# TwoArmedBandit_old.net
KiCad netlist of a schematic drawn in EAGLE
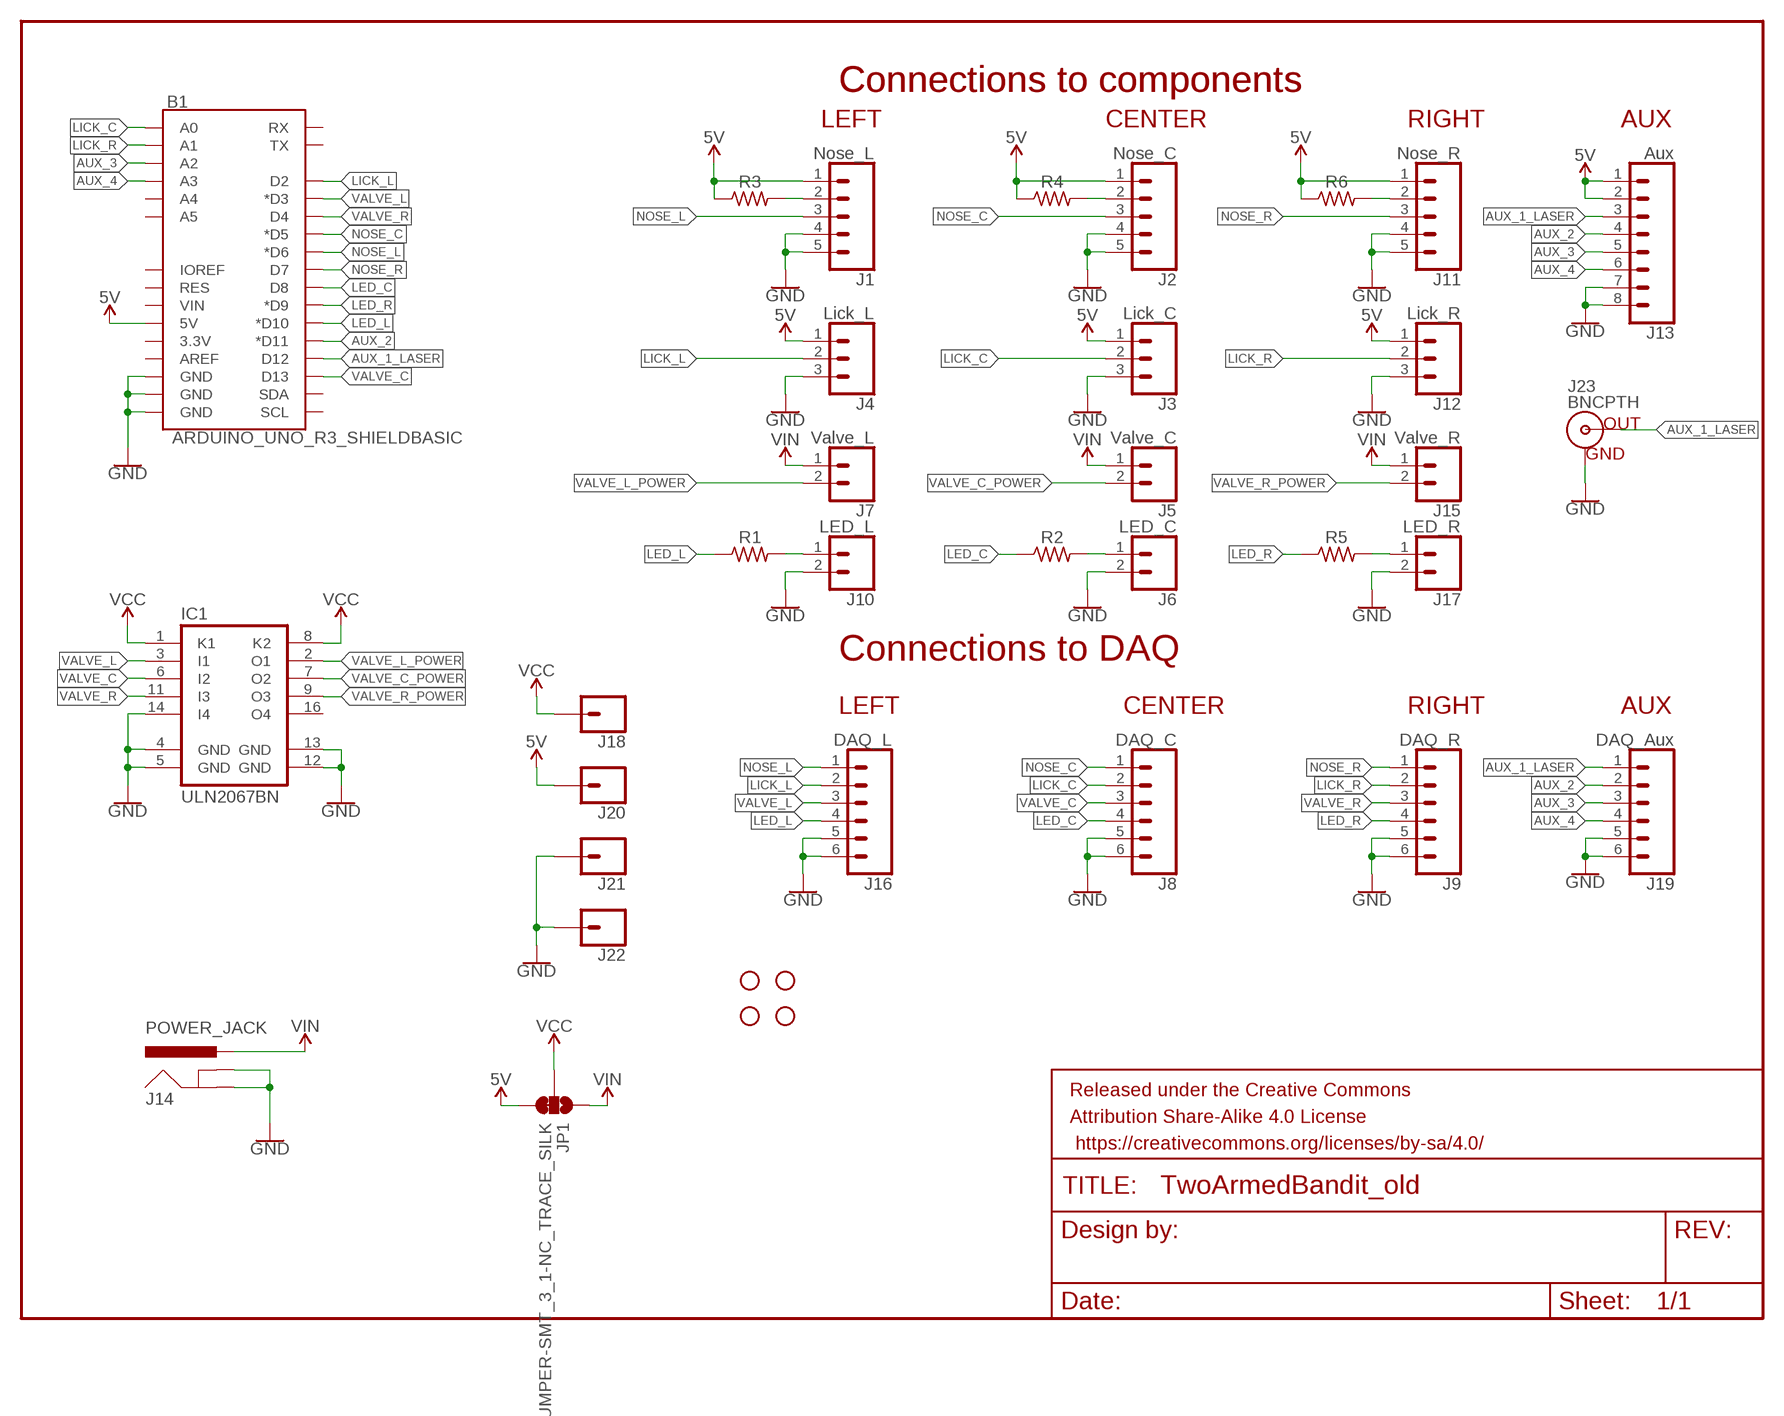
[diagram p0: schematic, sheet 1]

(export (version "E")
  (design (tool "Eeschema 10.0.6"))
  (components
    (comp (ref "B1")
      (value "ARDUINO_UNO_R3_SHIELDBASIC")
      (footprint "eagle-import:UNO_R3_SHIELD")
      (libsource (lib "eagle-import") (part "ARDUINO_UNO_R3_SHIELDBASIC"))
    )
    (comp (ref "FRAME1")
      (value "FRAME-LETTERNO_PACKAGE")
      (footprint "eagle-import:DUMMY")
      (fields (field (name "DESIGNER") "Nobody"))
      (libsource (lib "eagle-import") (part "FRAME-LETTERNO_PACKAGE"))
    )
    (comp (ref "H1")
      (value "STAND-OFF")
      (footprint "eagle-import:STAND-OFF")
      (libsource (lib "eagle-import") (part "STAND-OFF"))
    )
    (comp (ref "H2")
      (value "STAND-OFF")
      (footprint "eagle-import:STAND-OFF")
      (libsource (lib "eagle-import") (part "STAND-OFF"))
    )
    (comp (ref "H3")
      (value "STAND-OFF")
      (footprint "eagle-import:STAND-OFF")
      (libsource (lib "eagle-import") (part "STAND-OFF"))
    )
    (comp (ref "H4")
      (value "STAND-OFF")
      (footprint "eagle-import:STAND-OFF")
      (libsource (lib "eagle-import") (part "STAND-OFF"))
    )
    (comp (ref "IC1")
      (value "ULN2067BN")
      (footprint "eagle-import:DIL16")
      (libsource (lib "eagle-import") (part "ULN2067BN"))
    )
    (comp (ref "J1")
      (value "Nose_L")
      (footprint "eagle-import:SCREWTERMINAL-3.5MM-5")
      (libsource (lib "eagle-import") (part "CONN_05SCREW"))
    )
    (comp (ref "J2")
      (value "Nose_C")
      (footprint "eagle-import:SCREWTERMINAL-3.5MM-5")
      (libsource (lib "eagle-import") (part "CONN_05SCREW"))
    )
    (comp (ref "J3")
      (value "Lick_C")
      (footprint "eagle-import:1X03")
      (libsource (lib "eagle-import") (part "CONN_03"))
    )
    (comp (ref "J4")
      (value "Lick_L")
      (footprint "eagle-import:1X03")
      (libsource (lib "eagle-import") (part "CONN_03"))
    )
    (comp (ref "J5")
      (value "Valve_C")
      (footprint "eagle-import:1X02")
      (libsource (lib "eagle-import") (part "CONN_02"))
    )
    (comp (ref "J6")
      (value "LED_C")
      (footprint "eagle-import:1X02")
      (libsource (lib "eagle-import") (part "CONN_02"))
    )
    (comp (ref "J7")
      (value "Valve_L")
      (footprint "eagle-import:1X02")
      (libsource (lib "eagle-import") (part "CONN_02"))
    )
    (comp (ref "J8")
      (value "DAQ_C")
      (footprint "eagle-import:SCREWTERMINAL-3.5MM-6")
      (libsource (lib "eagle-import") (part "CONN_063.5MM-6"))
    )
    (comp (ref "J9")
      (value "DAQ_R")
      (footprint "eagle-import:SCREWTERMINAL-3.5MM-6")
      (libsource (lib "eagle-import") (part "CONN_063.5MM-6"))
    )
    (comp (ref "J10")
      (value "LED_L")
      (footprint "eagle-import:1X02")
      (libsource (lib "eagle-import") (part "CONN_02"))
    )
    (comp (ref "J11")
      (value "Nose_R")
      (footprint "eagle-import:SCREWTERMINAL-3.5MM-5")
      (libsource (lib "eagle-import") (part "CONN_05SCREW"))
    )
    (comp (ref "J12")
      (value "Lick_R")
      (footprint "eagle-import:1X03")
      (libsource (lib "eagle-import") (part "CONN_03"))
    )
    (comp (ref "J13")
      (value "Aux")
      (footprint "eagle-import:1X08")
      (libsource (lib "eagle-import") (part "CONN_08{dblquote}"))
    )
    (comp (ref "J14")
      (value "POWER_JACK")
      (footprint "eagle-import:POWER_JACK_PTH")
      (libsource (lib "eagle-import") (part "POWER_JACK"))
    )
    (comp (ref "J15")
      (value "Valve_R")
      (footprint "eagle-import:1X02")
      (libsource (lib "eagle-import") (part "CONN_02"))
    )
    (comp (ref "J16")
      (value "DAQ_L")
      (footprint "eagle-import:SCREWTERMINAL-3.5MM-6")
      (libsource (lib "eagle-import") (part "CONN_063.5MM-6"))
    )
    (comp (ref "J17")
      (value "LED_R")
      (footprint "eagle-import:1X02")
      (libsource (lib "eagle-import") (part "CONN_02"))
    )
    (comp (ref "J18")
      (value "CONN_01PTH_2MM")
      (footprint "eagle-import:1X01_2MM")
      (libsource (lib "eagle-import") (part "CONN_01PTH_2MM"))
    )
    (comp (ref "J19")
      (value "DAQ_Aux")
      (footprint "eagle-import:SCREWTERMINAL-3.5MM-6")
      (libsource (lib "eagle-import") (part "CONN_063.5MM-6"))
    )
    (comp (ref "J20")
      (value "CONN_01PTH_2MM")
      (footprint "eagle-import:1X01_2MM")
      (libsource (lib "eagle-import") (part "CONN_01PTH_2MM"))
    )
    (comp (ref "J21")
      (value "CONN_01PTH_2MM")
      (footprint "eagle-import:1X01_2MM")
      (libsource (lib "eagle-import") (part "CONN_01PTH_2MM"))
    )
    (comp (ref "J22")
      (value "CONN_01PTH_2MM")
      (footprint "eagle-import:1X01_2MM")
      (libsource (lib "eagle-import") (part "CONN_01PTH_2MM"))
    )
    (comp (ref "J23")
      (value "BNCPTH")
      (footprint "eagle-import:BNC")
      (libsource (lib "eagle-import") (part "BNCPTH"))
    )
    (comp (ref "JP1")
      (value "JUMPER-SMT_3_1-NC_TRACE_SILK")
      (footprint "eagle-import:SMT-JUMPER_3_1-NC_TRACE_SILK")
      (libsource (lib "eagle-import") (part "JUMPER-SMT_3_1-NC_TRACE_SILK"))
    )
    (comp (ref "R1")
      (value "330")
      (footprint "eagle-import:0309_12")
      (libsource (lib "eagle-import") (part "R-US_0309/12"))
    )
    (comp (ref "R2")
      (value "330")
      (footprint "eagle-import:0309_12")
      (libsource (lib "eagle-import") (part "R-US_0309/12"))
    )
    (comp (ref "R3")
      (value "160")
      (footprint "eagle-import:0309_12")
      (libsource (lib "eagle-import") (part "R-US_0309/12"))
    )
    (comp (ref "R4")
      (value "160")
      (footprint "eagle-import:0309_12")
      (libsource (lib "eagle-import") (part "R-US_0309/12"))
    )
    (comp (ref "R5")
      (value "330")
      (footprint "eagle-import:0309_12")
      (libsource (lib "eagle-import") (part "R-US_0309/12"))
    )
    (comp (ref "R6")
      (value "160")
      (footprint "eagle-import:0309_12")
      (libsource (lib "eagle-import") (part "R-US_0309/12"))
    )
  )
  (nets
    (net (code "1") (name "5V") (class "Default")
      (node (ref "B1") (pin "5V") (pinfunction "5V_5V") (pintype "bidirectional"))
      (node (ref "J1") (pin "1") (pinfunction "1_1") (pintype "passive"))
      (node (ref "J11") (pin "1") (pinfunction "1_1") (pintype "passive"))
      (node (ref "J12") (pin "1") (pinfunction "1_1") (pintype "passive"))
      (node (ref "J13") (pin "1") (pinfunction "1_1") (pintype "passive"))
      (node (ref "J13") (pin "2") (pinfunction "2_2") (pintype "passive"))
      (node (ref "J2") (pin "1") (pinfunction "1_1") (pintype "passive"))
      (node (ref "J20") (pin "1") (pinfunction "1_1") (pintype "passive"))
      (node (ref "J3") (pin "1") (pinfunction "1_1") (pintype "passive"))
      (node (ref "J4") (pin "1") (pinfunction "1_1") (pintype "passive"))
      (node (ref "JP1") (pin "3") (pinfunction "3_3") (pintype "passive"))
      (node (ref "R3") (pin "1") (pinfunction "1_1") (pintype "passive"))
      (node (ref "R4") (pin "1") (pinfunction "1_1") (pintype "passive"))
      (node (ref "R6") (pin "1") (pinfunction "1_1") (pintype "passive"))
    )
    (net (code "2") (name "AUX_1_LASER") (class "Default")
      (node (ref "B1") (pin "D12") (pinfunction "D12_D12") (pintype "bidirectional"))
      (node (ref "J13") (pin "3") (pinfunction "3_3") (pintype "passive"))
      (node (ref "J19") (pin "1") (pinfunction "1_1") (pintype "passive"))
      (node (ref "J23") (pin "S") (pinfunction "OUT_S") (pintype "bidirectional"))
    )
    (net (code "3") (name "AUX_2") (class "Default")
      (node (ref "B1") (pin "D11") (pinfunction "*D11_D11") (pintype "bidirectional"))
      (node (ref "J13") (pin "4") (pinfunction "4_4") (pintype "passive"))
      (node (ref "J19") (pin "2") (pinfunction "2_2") (pintype "passive"))
    )
    (net (code "4") (name "AUX_3") (class "Default")
      (node (ref "B1") (pin "A2") (pinfunction "A2_A2") (pintype "bidirectional"))
      (node (ref "J13") (pin "5") (pinfunction "5_5") (pintype "passive"))
      (node (ref "J19") (pin "3") (pinfunction "3_3") (pintype "passive"))
    )
    (net (code "5") (name "AUX_4") (class "Default")
      (node (ref "B1") (pin "A3") (pinfunction "A3_A3") (pintype "bidirectional"))
      (node (ref "J13") (pin "6") (pinfunction "6_6") (pintype "passive"))
      (node (ref "J19") (pin "4") (pinfunction "4_4") (pintype "passive"))
    )
    (net (code "6") (name "GND") (class "Default")
      (node (ref "B1") (pin "GND@0") (pinfunction "GND_GND@0") (pintype "bidirectional"))
      (node (ref "B1") (pin "GND@1") (pinfunction "GND_GND@1") (pintype "bidirectional"))
      (node (ref "B1") (pin "GND@2") (pinfunction "GND_GND@2") (pintype "bidirectional"))
      (node (ref "IC1") (pin "12") (pinfunction "GND_12") (pintype "power_in"))
      (node (ref "IC1") (pin "13") (pinfunction "GND_13") (pintype "power_in"))
      (node (ref "IC1") (pin "14") (pinfunction "I4_14") (pintype "input"))
      (node (ref "IC1") (pin "4") (pinfunction "GND_4") (pintype "power_in"))
      (node (ref "IC1") (pin "5") (pinfunction "GND_5") (pintype "power_in"))
      (node (ref "J1") (pin "4") (pinfunction "4_4") (pintype "passive"))
      (node (ref "J1") (pin "5") (pinfunction "5_5") (pintype "passive"))
      (node (ref "J10") (pin "2") (pinfunction "2_2") (pintype "passive"))
      (node (ref "J11") (pin "4") (pinfunction "4_4") (pintype "passive"))
      (node (ref "J11") (pin "5") (pinfunction "5_5") (pintype "passive"))
      (node (ref "J12") (pin "3") (pinfunction "3_3") (pintype "passive"))
      (node (ref "J13") (pin "7") (pinfunction "7_7") (pintype "passive"))
      (node (ref "J13") (pin "8") (pinfunction "8_8") (pintype "passive"))
      (node (ref "J14") (pin "GND") (pinfunction "GND_GND") (pintype "bidirectional"))
      (node (ref "J14") (pin "GNDBREAK") (pinfunction "GNDBREAK_GNDBREAK") (pintype "bidirectional"))
      (node (ref "J16") (pin "5") (pinfunction "5_5") (pintype "passive"))
      (node (ref "J16") (pin "6") (pinfunction "6_6") (pintype "passive"))
      (node (ref "J17") (pin "2") (pinfunction "2_2") (pintype "passive"))
      (node (ref "J19") (pin "5") (pinfunction "5_5") (pintype "passive"))
      (node (ref "J19") (pin "6") (pinfunction "6_6") (pintype "passive"))
      (node (ref "J2") (pin "4") (pinfunction "4_4") (pintype "passive"))
      (node (ref "J2") (pin "5") (pinfunction "5_5") (pintype "passive"))
      (node (ref "J21") (pin "1") (pinfunction "1_1") (pintype "passive"))
      (node (ref "J22") (pin "1") (pinfunction "1_1") (pintype "passive"))
      (node (ref "J23") (pin "GND") (pinfunction "GND_GND") (pintype "bidirectional"))
      (node (ref "J3") (pin "3") (pinfunction "3_3") (pintype "passive"))
      (node (ref "J4") (pin "3") (pinfunction "3_3") (pintype "passive"))
      (node (ref "J6") (pin "2") (pinfunction "2_2") (pintype "passive"))
      (node (ref "J8") (pin "5") (pinfunction "5_5") (pintype "passive"))
      (node (ref "J8") (pin "6") (pinfunction "6_6") (pintype "passive"))
      (node (ref "J9") (pin "5") (pinfunction "5_5") (pintype "passive"))
      (node (ref "J9") (pin "6") (pinfunction "6_6") (pintype "passive"))
    )
    (net (code "7") (name "LED_C") (class "Default")
      (node (ref "B1") (pin "D8") (pinfunction "D8_D8") (pintype "bidirectional"))
      (node (ref "J8") (pin "4") (pinfunction "4_4") (pintype "passive"))
      (node (ref "R2") (pin "1") (pinfunction "1_1") (pintype "passive"))
    )
    (net (code "8") (name "LED_L") (class "Default")
      (node (ref "B1") (pin "D10") (pinfunction "*D10_D10") (pintype "bidirectional"))
      (node (ref "J16") (pin "4") (pinfunction "4_4") (pintype "passive"))
      (node (ref "R1") (pin "1") (pinfunction "1_1") (pintype "passive"))
    )
    (net (code "9") (name "LED_R") (class "Default")
      (node (ref "B1") (pin "D9") (pinfunction "*D9_D9") (pintype "bidirectional"))
      (node (ref "J9") (pin "4") (pinfunction "4_4") (pintype "passive"))
      (node (ref "R5") (pin "1") (pinfunction "1_1") (pintype "passive"))
    )
    (net (code "10") (name "LICK_C") (class "Default")
      (node (ref "B1") (pin "A0") (pinfunction "A0_A0") (pintype "bidirectional"))
      (node (ref "J3") (pin "2") (pinfunction "2_2") (pintype "passive"))
      (node (ref "J8") (pin "2") (pinfunction "2_2") (pintype "passive"))
    )
    (net (code "11") (name "LICK_L") (class "Default")
      (node (ref "B1") (pin "D2") (pinfunction "D2_D2") (pintype "bidirectional"))
      (node (ref "J16") (pin "2") (pinfunction "2_2") (pintype "passive"))
      (node (ref "J4") (pin "2") (pinfunction "2_2") (pintype "passive"))
    )
    (net (code "12") (name "LICK_R") (class "Default")
      (node (ref "B1") (pin "A1") (pinfunction "A1_A1") (pintype "bidirectional"))
      (node (ref "J12") (pin "2") (pinfunction "2_2") (pintype "passive"))
      (node (ref "J9") (pin "2") (pinfunction "2_2") (pintype "passive"))
    )
    (net (code "13") (name "NOSE_C") (class "Default")
      (node (ref "B1") (pin "D5") (pinfunction "*D5_D5") (pintype "bidirectional"))
      (node (ref "J2") (pin "3") (pinfunction "3_3") (pintype "passive"))
      (node (ref "J8") (pin "1") (pinfunction "1_1") (pintype "passive"))
    )
    (net (code "14") (name "NOSE_L") (class "Default")
      (node (ref "B1") (pin "D6") (pinfunction "*D6_D6") (pintype "bidirectional"))
      (node (ref "J1") (pin "3") (pinfunction "3_3") (pintype "passive"))
      (node (ref "J16") (pin "1") (pinfunction "1_1") (pintype "passive"))
    )
    (net (code "15") (name "NOSE_R") (class "Default")
      (node (ref "B1") (pin "D7") (pinfunction "D7_D7") (pintype "bidirectional"))
      (node (ref "J11") (pin "3") (pinfunction "3_3") (pintype "passive"))
      (node (ref "J9") (pin "1") (pinfunction "1_1") (pintype "passive"))
    )
    (net (code "16") (name "Net-(J1-Pad2)") (class "Default")
      (node (ref "J1") (pin "2") (pinfunction "2_2") (pintype "passive"))
      (node (ref "R3") (pin "2") (pinfunction "2_2") (pintype "passive"))
    )
    (net (code "17") (name "Net-(J2-Pad2)") (class "Default")
      (node (ref "J2") (pin "2") (pinfunction "2_2") (pintype "passive"))
      (node (ref "R4") (pin "2") (pinfunction "2_2") (pintype "passive"))
    )
    (net (code "18") (name "Net-(J6-Pad1)") (class "Default")
      (node (ref "J6") (pin "1") (pinfunction "1_1") (pintype "passive"))
      (node (ref "R2") (pin "2") (pinfunction "2_2") (pintype "passive"))
    )
    (net (code "19") (name "Net-(J10-Pad1)") (class "Default")
      (node (ref "J10") (pin "1") (pinfunction "1_1") (pintype "passive"))
      (node (ref "R1") (pin "2") (pinfunction "2_2") (pintype "passive"))
    )
    (net (code "20") (name "Net-(J11-Pad2)") (class "Default")
      (node (ref "J11") (pin "2") (pinfunction "2_2") (pintype "passive"))
      (node (ref "R6") (pin "2") (pinfunction "2_2") (pintype "passive"))
    )
    (net (code "21") (name "Net-(J17-Pad1)") (class "Default")
      (node (ref "J17") (pin "1") (pinfunction "1_1") (pintype "passive"))
      (node (ref "R5") (pin "2") (pinfunction "2_2") (pintype "passive"))
    )
    (net (code "22") (name "VALVE_C") (class "Default")
      (node (ref "B1") (pin "D13") (pinfunction "D13_D13") (pintype "bidirectional"))
      (node (ref "IC1") (pin "6") (pinfunction "I2_6") (pintype "input"))
      (node (ref "J8") (pin "3") (pinfunction "3_3") (pintype "passive"))
    )
    (net (code "23") (name "VALVE_C_POWER") (class "Default")
      (node (ref "IC1") (pin "7") (pinfunction "O2_7") (pintype "open_collector"))
      (node (ref "J5") (pin "2") (pinfunction "2_2") (pintype "passive"))
    )
    (net (code "24") (name "VALVE_L") (class "Default")
      (node (ref "B1") (pin "D3") (pinfunction "*D3_D3") (pintype "bidirectional"))
      (node (ref "IC1") (pin "3") (pinfunction "I1_3") (pintype "input"))
      (node (ref "J16") (pin "3") (pinfunction "3_3") (pintype "passive"))
    )
    (net (code "25") (name "VALVE_L_POWER") (class "Default")
      (node (ref "IC1") (pin "2") (pinfunction "O1_2") (pintype "open_collector"))
      (node (ref "J7") (pin "2") (pinfunction "2_2") (pintype "passive"))
    )
    (net (code "26") (name "VALVE_R") (class "Default")
      (node (ref "B1") (pin "D4") (pinfunction "D4_D4") (pintype "bidirectional"))
      (node (ref "IC1") (pin "11") (pinfunction "I3_11") (pintype "input"))
      (node (ref "J9") (pin "3") (pinfunction "3_3") (pintype "passive"))
    )
    (net (code "27") (name "VALVE_R_POWER") (class "Default")
      (node (ref "IC1") (pin "9") (pinfunction "O3_9") (pintype "open_collector"))
      (node (ref "J15") (pin "2") (pinfunction "2_2") (pintype "passive"))
    )
    (net (code "28") (name "VCC") (class "Default")
      (node (ref "IC1") (pin "1") (pinfunction "K1_1") (pintype "passive"))
      (node (ref "IC1") (pin "8") (pinfunction "K2_8") (pintype "passive"))
      (node (ref "J18") (pin "1") (pinfunction "1_1") (pintype "passive"))
      (node (ref "JP1") (pin "2") (pinfunction "2_2") (pintype "passive"))
    )
    (net (code "29") (name "VIN") (class "Default")
      (node (ref "J14") (pin "PWR") (pinfunction "PWR_PWR") (pintype "bidirectional"))
      (node (ref "J15") (pin "1") (pinfunction "1_1") (pintype "passive"))
      (node (ref "J5") (pin "1") (pinfunction "1_1") (pintype "passive"))
      (node (ref "J7") (pin "1") (pinfunction "1_1") (pintype "passive"))
      (node (ref "JP1") (pin "1") (pinfunction "1_1") (pintype "passive"))
    )
    (net (code "30") (name "unconnected-(B1-Pad3.3V)") (class "Default")
      (node (ref "B1") (pin "3.3V") (pinfunction "3.3V_3.3V") (pintype "bidirectional"))
    )
    (net (code "31") (name "unconnected-(B1-PadA4)") (class "Default")
      (node (ref "B1") (pin "A4") (pinfunction "A4_A4") (pintype "bidirectional"))
    )
    (net (code "32") (name "unconnected-(B1-PadA5)") (class "Default")
      (node (ref "B1") (pin "A5") (pinfunction "A5_A5") (pintype "bidirectional"))
    )
    (net (code "33") (name "unconnected-(B1-PadAREF)") (class "Default")
      (node (ref "B1") (pin "AREF") (pinfunction "AREF_AREF") (pintype "bidirectional"))
    )
    (net (code "34") (name "unconnected-(B1-PadIOREF)") (class "Default")
      (node (ref "B1") (pin "IOREF") (pinfunction "IOREF_IOREF") (pintype "bidirectional"))
    )
    (net (code "35") (name "unconnected-(B1-PadRES)") (class "Default")
      (node (ref "B1") (pin "RES") (pinfunction "RES_RES") (pintype "bidirectional"))
    )
    (net (code "36") (name "unconnected-(B1-PadRX)") (class "Default")
      (node (ref "B1") (pin "RX") (pinfunction "RX_RX") (pintype "bidirectional"))
    )
    (net (code "37") (name "unconnected-(B1-PadSCL)") (class "Default")
      (node (ref "B1") (pin "SCL") (pinfunction "SCL_SCL") (pintype "bidirectional"))
    )
    (net (code "38") (name "unconnected-(B1-PadSDA)") (class "Default")
      (node (ref "B1") (pin "SDA") (pinfunction "SDA_SDA") (pintype "bidirectional"))
    )
    (net (code "39") (name "unconnected-(B1-PadTX)") (class "Default")
      (node (ref "B1") (pin "TX") (pinfunction "TX_TX") (pintype "bidirectional"))
    )
    (net (code "40") (name "unconnected-(B1-PadVIN)") (class "Default")
      (node (ref "B1") (pin "VIN") (pinfunction "VIN_VIN") (pintype "bidirectional"))
    )
    (net (code "41") (name "unconnected-(IC1-O4-Pad16)") (class "Default")
      (node (ref "IC1") (pin "16") (pinfunction "O4_16") (pintype "open_collector"))
    )
  )
)
